# AnalogInterface.net
KiCad netlist of a schematic drawn in Altium Designer
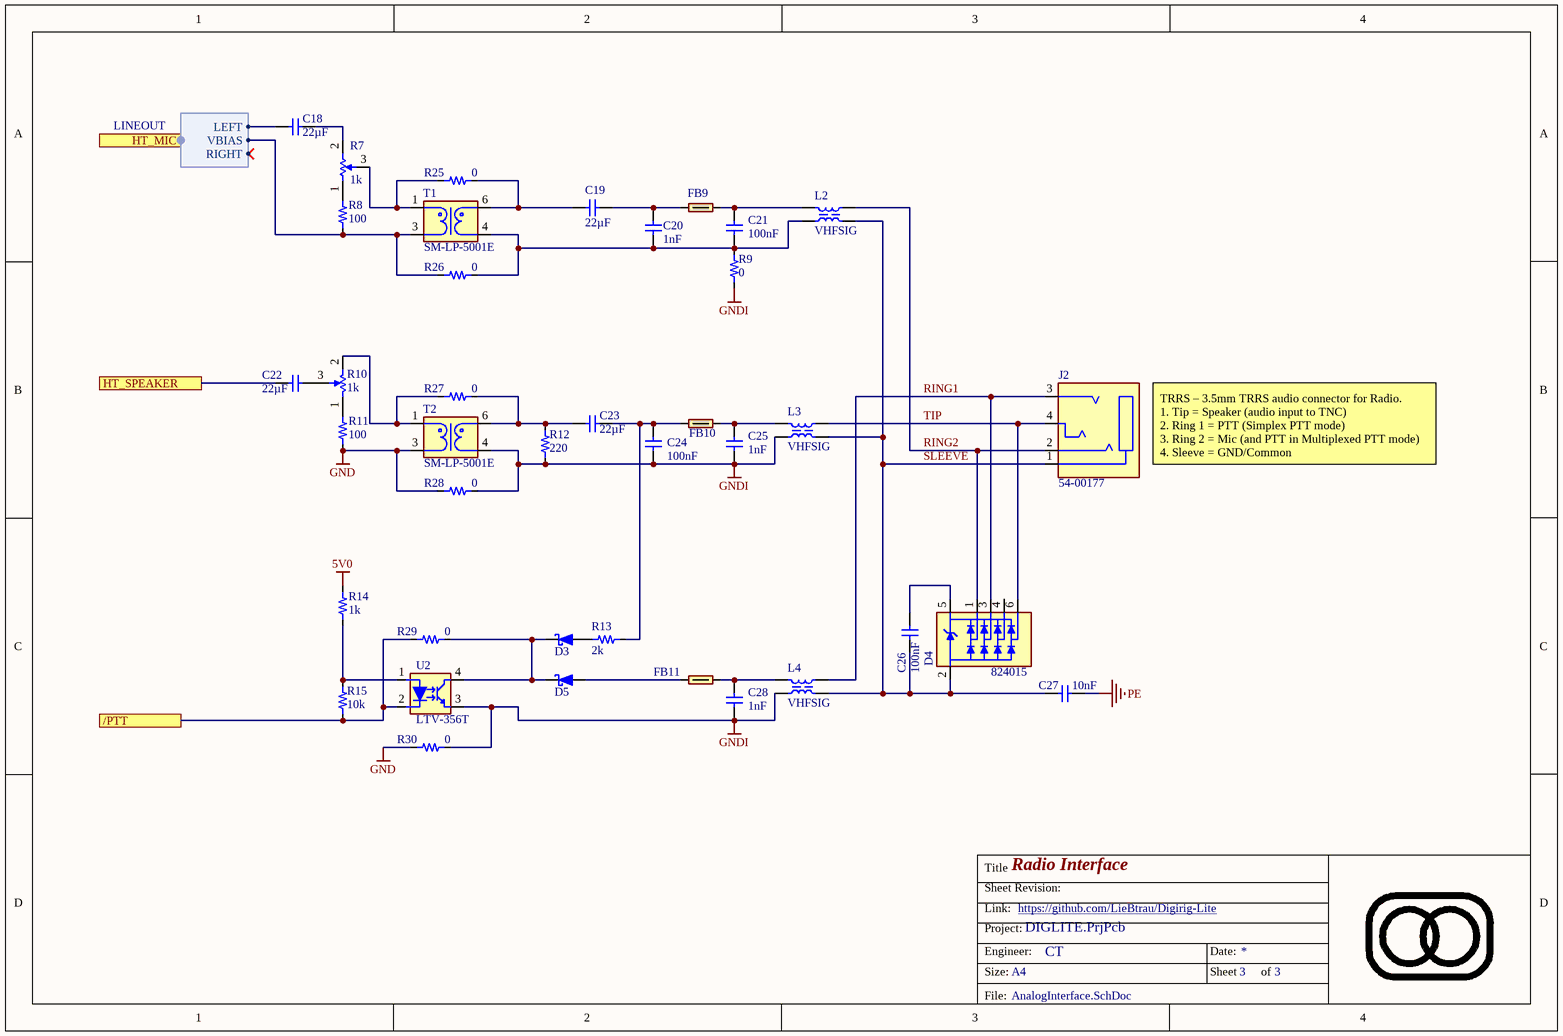
[diagram p0: AnalogInterface.SchDoc]

(export (version "E")
  (design (tool "Eeschema 10.0.6"))
  (components
    (comp (ref "C18")
      (value "22µF")
      (footprint "WCAP-CSGP_1210_L3.2W2.5H2.5")
      (description "WCAP-CSGP Multilayer Ceramic Chip Capacitor, General Purpose, size 1210, X7R, 22µF, 10VDC")
      (fields (field (name "TOLERANCE") "10%") (field (name "JLCPCB PART #") "C515687"))
      (libsource (lib "7c7 Engineering") (part "CAP-NP-2"))
    )
    (comp (ref "C19")
      (value "22µF")
      (footprint "WCAP-CSGP_1210_L3.2W2.5H2.5")
      (description "WCAP-CSGP Multilayer Ceramic Chip Capacitor, General Purpose, size 1210, X7R, 22µF, 10VDC")
      (fields (field (name "TOLERANCE") "10%") (field (name "JLCPCB PART #") "C515687"))
      (libsource (lib "7c7 Engineering") (part "CAP-NP-2"))
    )
    (comp (ref "C20")
      (value "1nF")
      (footprint "0603-C-N")
      (description "Capacitor MLCC, General Purpose, size 0603, C0G, 1 nF, +/-5%, 50V")
      (fields (field (name "TOLERANCE") "5%") (field (name "JLCPCB PART #") "C340644"))
      (libsource (lib "7c7 Engineering") (part "CAP-NP-2"))
    )
    (comp (ref "C21")
      (value "100nF")
      (footprint "0603-C-N")
      (description "WCAP-CSGP Multilayer Ceramic Chip Capacitor, General Purpose, size 0603, X7R, 100nF, 50VDC")
      (fields (field (name "TOLERANCE") "10%") (field (name "JLCPCB PART #") "C14663"))
      (libsource (lib "7c7 Engineering") (part "CAP-NP-2"))
    )
    (comp (ref "C22")
      (value "22µF")
      (footprint "WCAP-CSGP_1210_L3.2W2.5H2.5")
      (description "WCAP-CSGP Multilayer Ceramic Chip Capacitor, General Purpose, size 1210, X7R, 22µF, 10VDC")
      (fields (field (name "TOLERANCE") "10%") (field (name "JLCPCB PART #") "C515687"))
      (libsource (lib "7c7 Engineering") (part "CAP-NP-2"))
    )
    (comp (ref "C23")
      (value "22µF")
      (footprint "WCAP-CSGP_1210_L3.2W2.5H2.5")
      (description "WCAP-CSGP Multilayer Ceramic Chip Capacitor, General Purpose, size 1210, X7R, 22µF, 10VDC")
      (fields (field (name "TOLERANCE") "10%") (field (name "JLCPCB PART #") "C515687"))
      (libsource (lib "7c7 Engineering") (part "CAP-NP-2"))
    )
    (comp (ref "C24")
      (value "100nF")
      (footprint "0603-C-N")
      (description "WCAP-CSGP Multilayer Ceramic Chip Capacitor, General Purpose, size 0603, X7R, 100nF, 50VDC")
      (fields (field (name "TOLERANCE") "10%") (field (name "JLCPCB PART #") "C14663"))
      (libsource (lib "7c7 Engineering") (part "CAP-NP-2"))
    )
    (comp (ref "C25")
      (value "1nF")
      (footprint "0603-C-N")
      (description "Capacitor MLCC, General Purpose, size 0603, C0G, 1 nF, +/-5%, 50V")
      (fields (field (name "TOLERANCE") "5%") (field (name "JLCPCB PART #") "C340644"))
      (libsource (lib "7c7 Engineering") (part "CAP-NP-2"))
    )
    (comp (ref "C26")
      (value "100nF")
      (footprint "0603-C-N")
      (description "WCAP-CSGP Multilayer Ceramic Chip Capacitor, General Purpose, size 0603, X7R, 100nF, 50VDC")
      (fields (field (name "TOLERANCE") "10%") (field (name "JLCPCB PART #") "C14663"))
      (libsource (lib "7c7 Engineering") (part "CAP-NP-2"))
    )
    (comp (ref "C27")
      (value "10nF")
      (footprint "0603-C-N")
      (description "Multilayer Ceramic Capacitor, Grm Series, 0.01 F, 5%, C0g / Np0, 50 V, 0603 [1608 Metric]")
      (fields (field (name "VOLTAGE") "50V") (field (name "TOLERANCE") "5%"))
      (libsource (lib "7c7 Engineering") (part "CAP-NP-2"))
    )
    (comp (ref "C28")
      (value "1nF")
      (footprint "0603-C-N")
      (description "Capacitor MLCC, General Purpose, size 0603, C0G, 1 nF, +/-5%, 50V")
      (fields (field (name "TOLERANCE") "5%") (field (name "JLCPCB PART #") "C340644"))
      (libsource (lib "7c7 Engineering") (part "CAP-NP-2"))
    )
    (comp (ref "D3")
      (value "RB521SM-30T2R")
      (footprint "FP-SOD523-MFG")
      (description "RB521SM Series 30 V 200 mA Surface Mount Schottky Barrier Diode -SOD-523 (SC-79)")
      (fields (field (name "JLCPCB PART #") "C727120"))
      (libsource (lib "7c7 Engineering") (part "DIODE-SKY-2"))
    )
    (comp (ref "D4")
      (value "824015")
      (footprint "SOT-23-6")
      (description "WE-TVS TVS Diode - High Speed Series, SOT23-6L, 4+1Channel, 5Vdc")
      (fields (field (name "FLIR PART #") "YDITA20KV100A") (field (name "JLCPCB PART #") "C558418"))
      (libsource (lib "7c7 Engineering") (part "D-TVS-4CH"))
    )
    (comp (ref "D5")
      (value "RB521SM-30T2R")
      (footprint "FP-SOD523-MFG")
      (description "RB521SM Series 30 V 200 mA Surface Mount Schottky Barrier Diode -SOD-523 (SC-79)")
      (fields (field (name "JLCPCB PART #") "C727120"))
      (libsource (lib "7c7 Engineering") (part "DIODE-SKY-2"))
    )
    (comp (ref "FB9")
      (value "742792662")
      (footprint "0603-FB-N")
      (description "WE-CBF SMT EMI Suppression Ferrite Bead, size 0603, 1000O, 0.83A")
      (fields (field (name "JLCPCB PART #") "C180490") (field (name "MANUFACTURER") "Wurth Elektronik"))
      (libsource (lib "") (part "IND_BEAD_1"))
    )
    (comp (ref "FB10")
      (value "742792662")
      (footprint "0603-FB-N")
      (description "WE-CBF SMT EMI Suppression Ferrite Bead, size 0603, 1000O, 0.83A")
      (fields (field (name "JLCPCB PART #") "C180490") (field (name "MANUFACTURER") "Wurth Elektronik"))
      (libsource (lib "7c7 Engineering") (part "IND_BEAD"))
    )
    (comp (ref "FB11")
      (value "742792662")
      (footprint "0603-FB-N")
      (description "WE-CBF SMT EMI Suppression Ferrite Bead, size 0603, 1000O, 0.83A")
      (fields (field (name "JLCPCB PART #") "C180490") (field (name "MANUFACTURER") "Wurth Elektronik"))
      (libsource (lib "") (part "IND_BEAD_1"))
    )
    (comp (ref "J2")
      (value "54-00177")
      (footprint "54-00177-Footprint-1")
      (description "Conn Jack 4 Cond 3.5MM SMD R/a")
      (fields (field (name "JLCPCB PART #") "C7507452"))
      (libsource (lib "7c7 Engineering") (part "CN_AUDIO_JACK_TRRS_NO_SWITCH"))
    )
    (comp (ref "L2")
      (value "VHFSIG")
      (footprint "WE-CNSW_1206")
      (description "WE-CNSW SMT Common Mode Line Filter, size 1206, 2200Ohm@100MHz, 1-300MHz, 200mA, 1.2ohm")
      (fields (field (name "JLCPCB PART #") "C3211563") (field (name "PAGE PART #") "L744232222"))
      (libsource (lib "7c7 Engineering") (part "CM-choke"))
    )
    (comp (ref "L3")
      (value "VHFSIG")
      (footprint "WE-CNSW_1206")
      (description "WE-CNSW SMT Common Mode Line Filter, size 1206, 2200Ohm@100MHz, 1-300MHz, 200mA, 1.2ohm")
      (fields (field (name "JLCPCB PART #") "C3211563") (field (name "PAGE PART #") "L744232222"))
      (libsource (lib "7c7 Engineering") (part "CM-choke"))
    )
    (comp (ref "L4")
      (value "VHFSIG")
      (footprint "WE-CNSW_1206")
      (description "WE-CNSW SMT Common Mode Line Filter, size 1206, 2200Ohm@100MHz, 1-300MHz, 200mA, 1.2ohm")
      (fields (field (name "JLCPCB PART #") "C3211563") (field (name "PAGE PART #") "L744232222"))
      (libsource (lib "7c7 Engineering") (part "CM-choke"))
    )
    (comp (ref "R7")
      (value "1k")
      (footprint "3314G-1-102E-Footprint-1")
      (description "Cermet trimmer potentiometer, 1 kΩ, 0.25 W, SMD, on top, 3314G-1-102E")
      (fields (field (name "TOLERANCE") "20%") (field (name "JLCPCB PART #") "C780221"))
      (libsource (lib "7c7 Engineering") (part "RES-ADJ-3"))
    )
    (comp (ref "R8")
      (value "100")
      (footprint "0603-R-N")
      (description "Chip Resistor, Thick Film, General Purpose, 0603, 63mW, 50V, 100 Ohm, +/-1%")
      (fields (field (name "JLCPCB PART #") "C22775") (field (name "TOLERANCE") "1%"))
      (libsource (lib "7c7 Engineering") (part "RES"))
    )
    (comp (ref "R9")
      (value "0")
      (footprint "0603-R-N")
      (description "Chip Jumper, Thick Film, Jumper, 0603, 100mW, 1A, 0 Ohm, <50 mOhm")
      (fields (field (name "FLIR PART #") "YRES0E-1") (field (name "TOLERANCE") "50 mOhm"))
      (libsource (lib "7c7 Engineering") (part "RES"))
    )
    (comp (ref "R10")
      (value "1k")
      (footprint "3314G-1-102E-Footprint-1")
      (description "Cermet trimmer potentiometer, 1 kΩ, 0.25 W, SMD, on top, 3314G-1-102E")
      (fields (field (name "TOLERANCE") "20%") (field (name "JLCPCB PART #") "C780221"))
      (libsource (lib "7c7 Engineering") (part "RES-ADJ-3"))
    )
    (comp (ref "R11")
      (value "100")
      (footprint "0603-R-N")
      (description "Chip Resistor, Thick Film, General Purpose, 0603, 63mW, 50V, 100 Ohm, +/-1%")
      (fields (field (name "JLCPCB PART #") "C22775") (field (name "TOLERANCE") "1%"))
      (libsource (lib "7c7 Engineering") (part "RES"))
    )
    (comp (ref "R12")
      (value "220")
      (footprint "0603-R-N")
      (description "Res Thick Film 0603 220 Ohm 1% 0.1W(1/10W) ±100ppm/C Pad SMD T/R Automotive AEC-Q200")
      (fields (field (name "TOLERANCE") "1%") (field (name "JLCPCB PART #") "C22962"))
      (libsource (lib "7c7 Engineering") (part "RES"))
    )
    (comp (ref "R13")
      (value "2k")
      (footprint "0603-R-N")
      (description "Chip Resistor, Thick Film, General Purpose, 0603, 100mW, 50V, 2 kOhm, +/-1%")
      (fields (field (name "JLCPCB PART #") "C22975") (field (name "TOLERANCE") "1%"))
      (libsource (lib "7c7 Engineering") (part "RES"))
    )
    (comp (ref "R14")
      (value "1k")
      (footprint "0603-R-N")
      (description "Chip Resistor, Thick Film, General Purpose, 0603, 100mW, 50V, 1 kOhm, +/-1%")
      (fields (field (name "JLCPCB PART #") "C21190") (field (name "TOLERANCE") "1%"))
      (libsource (lib "7c7 Engineering") (part "RES"))
    )
    (comp (ref "R15")
      (value "10k")
      (footprint "0603-R-N")
      (description "Chip Resistor, Thick Film, General Purpose, 0603, 100mW, 50V, 10 kOhm, +/-1%")
      (fields (field (name "FLIR PART #") "YRES10K-1") (field (name "PAGE PART #") "ROQF1002"))
      (libsource (lib "7c7 Engineering") (part "RES"))
    )
    (comp (ref "R25")
      (value "0")
      (footprint "0603-R-N")
      (description "Chip Jumper, Thick Film, Jumper, 0603, 100mW, 1A, 0 Ohm, <50 mOhm")
      (fields (field (name "FLIR PART #") "YRES0E-1") (field (name "TOLERANCE") "50 mOhm"))
      (libsource (lib "7c7 Engineering") (part "RES"))
    )
    (comp (ref "R26")
      (value "0")
      (footprint "0603-R-N")
      (description "Chip Jumper, Thick Film, Jumper, 0603, 100mW, 1A, 0 Ohm, <50 mOhm")
      (fields (field (name "FLIR PART #") "YRES0E-1") (field (name "TOLERANCE") "50 mOhm"))
      (libsource (lib "7c7 Engineering") (part "RES"))
    )
    (comp (ref "R27")
      (value "0")
      (footprint "0603-R-N")
      (description "Chip Jumper, Thick Film, Jumper, 0603, 100mW, 1A, 0 Ohm, <50 mOhm")
      (fields (field (name "FLIR PART #") "YRES0E-1") (field (name "TOLERANCE") "50 mOhm"))
      (libsource (lib "7c7 Engineering") (part "RES"))
    )
    (comp (ref "R28")
      (value "0")
      (footprint "0603-R-N")
      (description "Chip Jumper, Thick Film, Jumper, 0603, 100mW, 1A, 0 Ohm, <50 mOhm")
      (fields (field (name "FLIR PART #") "YRES0E-1") (field (name "TOLERANCE") "50 mOhm"))
      (libsource (lib "7c7 Engineering") (part "RES"))
    )
    (comp (ref "R29")
      (value "0")
      (footprint "0603-R-N")
      (description "Chip Jumper, Thick Film, Jumper, 0603, 100mW, 1A, 0 Ohm, <50 mOhm")
      (fields (field (name "FLIR PART #") "YRES0E-1") (field (name "TOLERANCE") "50 mOhm"))
      (libsource (lib "7c7 Engineering") (part "RES"))
    )
    (comp (ref "R30")
      (value "0")
      (footprint "0603-R-N")
      (description "Chip Jumper, Thick Film, Jumper, 0603, 100mW, 1A, 0 Ohm, <50 mOhm")
      (fields (field (name "FLIR PART #") "YRES0E-1") (field (name "TOLERANCE") "50 mOhm"))
      (libsource (lib "7c7 Engineering") (part "RES"))
    )
    (comp (ref "T1")
      (value "SM-LP-5001E")
      (footprint "FP-SM-LP-5001E-MFG")
      (description "Audio Transformer 1: 1 2000Vrms 115Ohm Prim. DCR 115Ohm Sec. DCR ±0.25dB 2dB Surface Mount")
      (fields (field (name "JLCPCB PART #") "C840532"))
      (libsource (lib "7c7 Engineering") (part "SM-LP-5001E"))
    )
    (comp (ref "T2")
      (value "SM-LP-5001E")
      (footprint "FP-SM-LP-5001E-MFG")
      (description "Audio Transformer 1: 1 2000Vrms 115Ohm Prim. DCR 115Ohm Sec. DCR ±0.25dB 2dB Surface Mount")
      (fields (field (name "JLCPCB PART #") "C840532"))
      (libsource (lib "7c7 Engineering") (part "SM-LP-5001E"))
    )
    (comp (ref "U2")
      (value "LTV-356T")
      (footprint "LTST-LTV-356T-4_V")
      (description "LTV Series Single Channel 80 V 3750 Vrms Transistor Output Optocoupler SMT DIP-4")
      (fields (field (name "JLCPCB PART #") "C125117") (field (name "PAGE PART #") "ZOCLTV356T"))
      (libsource (lib "7c7 Engineering") (part "OPTOCOUPLER"))
    )
  )
  (nets
    (net (code "2") (name "/HT_SPEAKER") (class "Default")
      (node (ref "C22") (pin "1") (pinfunction "1_1") (pintype "passive"))
    )
    (net (code "3") (name "/LEFT") (class "Default")
      (node (ref "C18") (pin "1") (pinfunction "1_1") (pintype "passive"))
    )
    (net (code "4") (name "/RING1") (class "Default")
      (node (ref "D4") (pin "3") (pinfunction "3_3") (pintype "passive"))
      (node (ref "J2") (pin "3") (pinfunction "3_3") (pintype "passive"))
      (node (ref "L4") (pin "4") (pinfunction "4_4") (pintype "passive"))
    )
    (net (code "5") (name "/RING2") (class "Default")
      (node (ref "D4") (pin "1") (pinfunction "1_1") (pintype "passive"))
      (node (ref "J2") (pin "2") (pinfunction "2_2") (pintype "passive"))
      (node (ref "L2") (pin "4") (pinfunction "4_4") (pintype "passive"))
    )
    (net (code "6") (name "/SLEEVE") (class "Default")
      (node (ref "C26") (pin "1") (pinfunction "1_1") (pintype "passive"))
      (node (ref "C27") (pin "2") (pinfunction "2_2") (pintype "passive"))
      (node (ref "D4") (pin "2") (pinfunction "2_2") (pintype "passive"))
      (node (ref "J2") (pin "1") (pinfunction "1_1") (pintype "passive"))
      (node (ref "L2") (pin "1") (pinfunction "1_1") (pintype "passive"))
      (node (ref "L3") (pin "1") (pinfunction "1_1") (pintype "passive"))
      (node (ref "L4") (pin "1") (pinfunction "1_1") (pintype "passive"))
    )
    (net (code "7") (name "/TIP") (class "Default")
      (node (ref "D4") (pin "6") (pinfunction "6_6") (pintype "passive"))
      (node (ref "J2") (pin "4") (pinfunction "4_4") (pintype "passive"))
      (node (ref "L3") (pin "4") (pinfunction "4_4") (pintype "passive"))
    )
    (net (code "8") (name "/VBIAS") (class "Default")
      (node (ref "R26") (pin "1") (pinfunction "1_1") (pintype "passive"))
      (node (ref "R8") (pin "2") (pinfunction "2_2") (pintype "passive"))
      (node (ref "T1") (pin "3") (pinfunction "3_3") (pintype "passive"))
    )
    (net (code "10") (name "/{slash}PTT") (class "Default")
      (node (ref "R15") (pin "1") (pinfunction "1_1") (pintype "passive"))
      (node (ref "R29") (pin "1") (pinfunction "1_1") (pintype "passive"))
      (node (ref "U2") (pin "2") (pinfunction "CATHODE_2") (pintype "passive"))
    )
    (net (code "11") (name "5V0") (class "Default")
      (node (ref "R14") (pin "1") (pinfunction "1_1") (pintype "passive"))
    )
    (net (code "12") (name "GND") (class "Default")
      (node (ref "R11") (pin "2") (pinfunction "2_2") (pintype "passive"))
      (node (ref "R28") (pin "1") (pinfunction "1_1") (pintype "passive"))
      (node (ref "R30") (pin "1") (pinfunction "1_1") (pintype "passive"))
      (node (ref "T2") (pin "3") (pinfunction "3_3") (pintype "passive"))
    )
    (net (code "13") (name "GNDI") (class "Default")
      (node (ref "C24") (pin "2") (pinfunction "2_2") (pintype "passive"))
      (node (ref "C25") (pin "2") (pinfunction "2_2") (pintype "passive"))
      (node (ref "C28") (pin "2") (pinfunction "2_2") (pintype "passive"))
      (node (ref "L3") (pin "2") (pinfunction "2_2") (pintype "passive"))
      (node (ref "L4") (pin "2") (pinfunction "2_2") (pintype "passive"))
      (node (ref "R12") (pin "1") (pinfunction "1_1") (pintype "passive"))
      (node (ref "R28") (pin "2") (pinfunction "2_2") (pintype "passive"))
      (node (ref "R30") (pin "2") (pinfunction "2_2") (pintype "passive"))
      (node (ref "R9") (pin "1") (pinfunction "1_1") (pintype "passive"))
      (node (ref "T2") (pin "4") (pinfunction "4_4") (pintype "passive"))
      (node (ref "U2") (pin "3") (pinfunction "EMITTER_3") (pintype "passive"))
    )
    (net (code "14") (name "Net-(C19-Pad1)") (class "Default")
      (node (ref "C19") (pin "1") (pinfunction "1_1") (pintype "passive"))
      (node (ref "C20") (pin "1") (pinfunction "1_1") (pintype "passive"))
      (node (ref "FB9") (pin "1") (pinfunction "1_1") (pintype "passive"))
    )
    (net (code "15") (name "Net-(C19-Pad2)") (class "Default")
      (node (ref "C19") (pin "2") (pinfunction "2_2") (pintype "passive"))
      (node (ref "R25") (pin "2") (pinfunction "2_2") (pintype "passive"))
      (node (ref "T1") (pin "6") (pinfunction "6_6") (pintype "passive"))
    )
    (net (code "16") (name "Net-(C20-Pad2)") (class "Default")
      (node (ref "C20") (pin "2") (pinfunction "2_2") (pintype "passive"))
      (node (ref "C21") (pin "2") (pinfunction "2_2") (pintype "passive"))
      (node (ref "L2") (pin "2") (pinfunction "2_2") (pintype "passive"))
      (node (ref "R26") (pin "2") (pinfunction "2_2") (pintype "passive"))
      (node (ref "R9") (pin "2") (pinfunction "2_2") (pintype "passive"))
      (node (ref "T1") (pin "4") (pinfunction "4_4") (pintype "passive"))
    )
    (net (code "17") (name "Net-(C21-Pad1)") (class "Default")
      (node (ref "C21") (pin "1") (pinfunction "1_1") (pintype "passive"))
      (node (ref "FB9") (pin "2") (pinfunction "2_2") (pintype "passive"))
      (node (ref "L2") (pin "3") (pinfunction "3_3") (pintype "passive"))
    )
    (net (code "18") (name "Net-(C23-Pad1)") (class "Default")
      (node (ref "C23") (pin "1") (pinfunction "1_1") (pintype "passive"))
      (node (ref "R12") (pin "2") (pinfunction "2_2") (pintype "passive"))
      (node (ref "R27") (pin "2") (pinfunction "2_2") (pintype "passive"))
      (node (ref "T2") (pin "6") (pinfunction "6_6") (pintype "passive"))
    )
    (net (code "19") (name "Net-(C23-Pad2)") (class "Default")
      (node (ref "C23") (pin "2") (pinfunction "2_2") (pintype "passive"))
      (node (ref "C24") (pin "1") (pinfunction "1_1") (pintype "passive"))
      (node (ref "FB10") (pin "2") (pinfunction "2_2") (pintype "passive"))
      (node (ref "R13") (pin "2") (pinfunction "2_2") (pintype "passive"))
    )
    (net (code "20") (name "Net-(C25-Pad1)") (class "Default")
      (node (ref "C25") (pin "1") (pinfunction "1_1") (pintype "passive"))
      (node (ref "FB10") (pin "1") (pinfunction "1_1") (pintype "passive"))
      (node (ref "L3") (pin "3") (pinfunction "3_3") (pintype "passive"))
    )
    (net (code "21") (name "Net-(C26-Pad2)") (class "Default")
      (node (ref "C26") (pin "2") (pinfunction "2_2") (pintype "passive"))
      (node (ref "D4") (pin "5") (pinfunction "5_5") (pintype "passive"))
    )
    (net (code "22") (name "Net-(C28-Pad1)") (class "Default")
      (node (ref "C28") (pin "1") (pinfunction "1_1") (pintype "passive"))
      (node (ref "FB11") (pin "2") (pinfunction "2_2") (pintype "passive"))
      (node (ref "L4") (pin "3") (pinfunction "3_3") (pintype "passive"))
    )
    (net (code "23") (name "Net-(D3-A)") (class "Default")
      (node (ref "D3") (pin "2") (pinfunction "A_2") (pintype "passive"))
      (node (ref "R13") (pin "1") (pinfunction "1_1") (pintype "passive"))
    )
    (net (code "24") (name "Net-(D3-K)") (class "Default")
      (node (ref "D3") (pin "1") (pinfunction "K_1") (pintype "passive"))
      (node (ref "D5") (pin "1") (pinfunction "K_1") (pintype "passive"))
      (node (ref "R29") (pin "2") (pinfunction "2_2") (pintype "passive"))
      (node (ref "U2") (pin "4") (pinfunction "COLLECTOR_4") (pintype "passive"))
    )
    (net (code "25") (name "Net-(D5-A)") (class "Default")
      (node (ref "D5") (pin "2") (pinfunction "A_2") (pintype "passive"))
      (node (ref "FB11") (pin "1") (pinfunction "1_1") (pintype "passive"))
    )
    (net (code "26") (name "Net-(R7-A)") (class "Default")
      (node (ref "R7") (pin "1") (pinfunction "A_1") (pintype "passive"))
      (node (ref "R8") (pin "1") (pinfunction "1_1") (pintype "passive"))
    )
    (net (code "27") (name "Net-(R7-B)") (class "Default")
      (node (ref "C18") (pin "2") (pinfunction "2_2") (pintype "passive"))
      (node (ref "R7") (pin "2") (pinfunction "B_2") (pintype "passive"))
    )
    (net (code "28") (name "Net-(R7-TAP)") (class "Default")
      (node (ref "R25") (pin "1") (pinfunction "1_1") (pintype "passive"))
      (node (ref "R7") (pin "3") (pinfunction "TAP_3") (pintype "passive"))
      (node (ref "T1") (pin "1") (pinfunction "1_1") (pintype "passive"))
    )
    (net (code "29") (name "Net-(R10-A)") (class "Default")
      (node (ref "R10") (pin "1") (pinfunction "A_1") (pintype "passive"))
      (node (ref "R11") (pin "1") (pinfunction "1_1") (pintype "passive"))
    )
    (net (code "30") (name "Net-(R10-B)") (class "Default")
      (node (ref "R10") (pin "2") (pinfunction "B_2") (pintype "passive"))
      (node (ref "R27") (pin "1") (pinfunction "1_1") (pintype "passive"))
      (node (ref "T2") (pin "1") (pinfunction "1_1") (pintype "passive"))
    )
    (net (code "31") (name "Net-(R10-TAP)") (class "Default")
      (node (ref "C22") (pin "2") (pinfunction "2_2") (pintype "passive"))
      (node (ref "R10") (pin "3") (pinfunction "TAP_3") (pintype "passive"))
    )
    (net (code "32") (name "Net-(U2-ANODE)") (class "Default")
      (node (ref "R14") (pin "2") (pinfunction "2_2") (pintype "passive"))
      (node (ref "R15") (pin "2") (pinfunction "2_2") (pintype "passive"))
      (node (ref "U2") (pin "1") (pinfunction "ANODE_1") (pintype "passive"))
    )
    (net (code "33") (name "PE") (class "Default")
      (node (ref "C27") (pin "1") (pinfunction "1_1") (pintype "passive"))
    )
    (net (code "34") (name "unconnected-(D4-Pad4)") (class "Default")
      (node (ref "D4") (pin "4") (pinfunction "4_4") (pintype "passive"))
    )
  )
)
